# 17_POWER-FILTER_LDO.net
KiCad netlist of a schematic drawn in Altium Designer
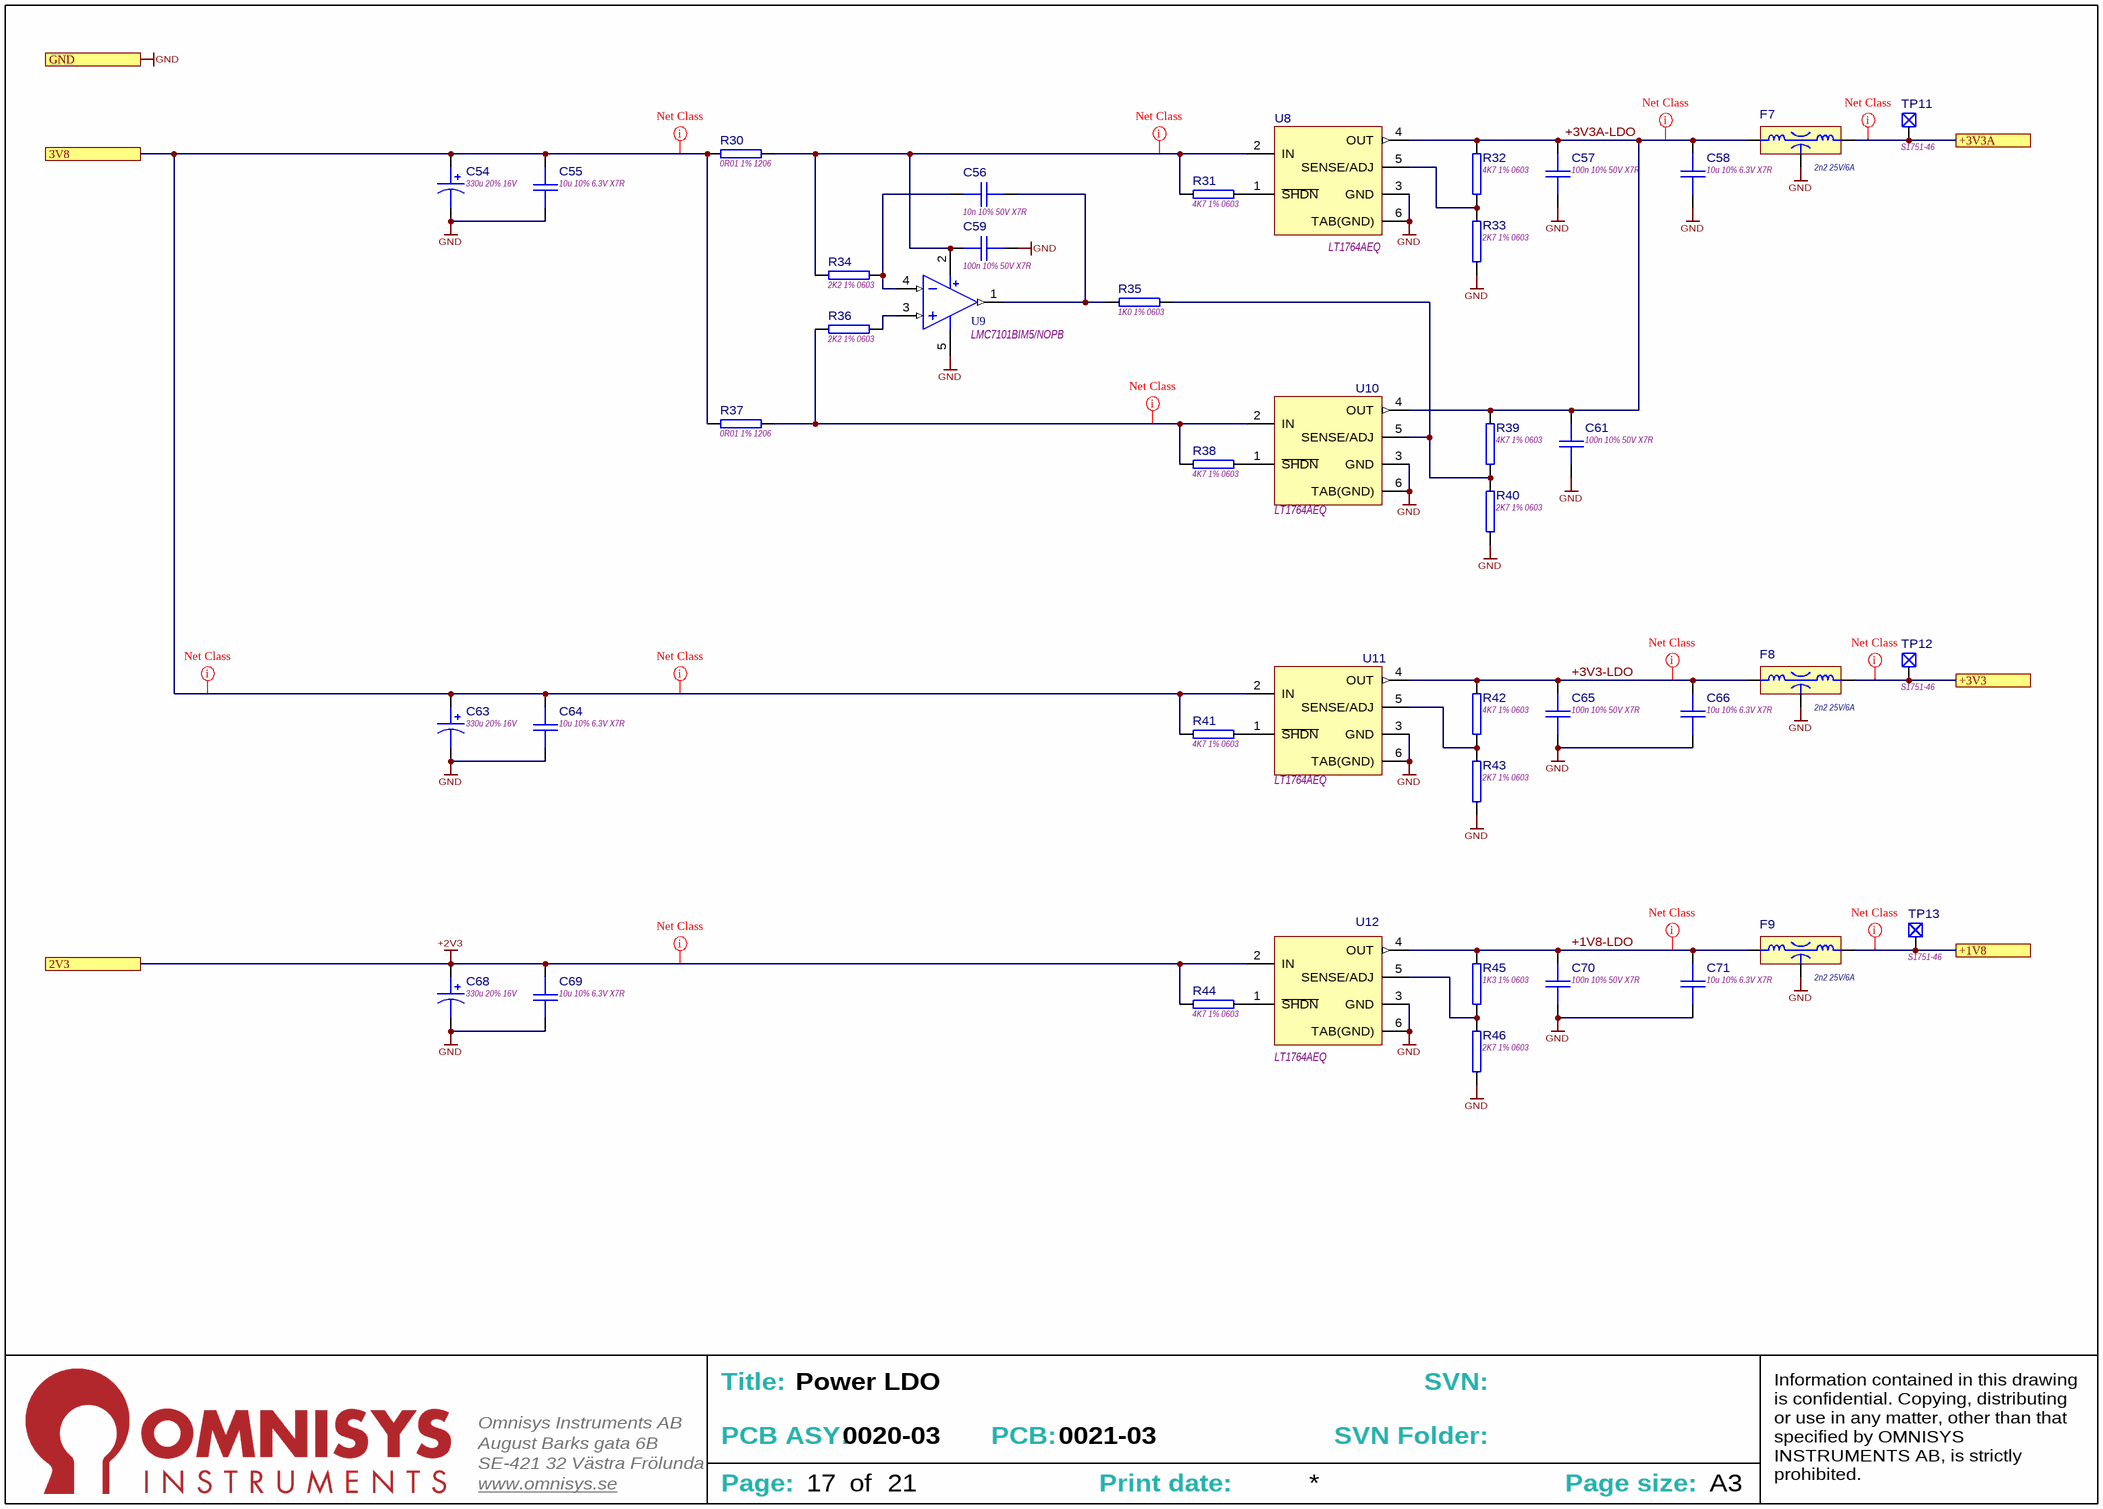
[diagram p0: [17] POWER-FILTER_LDO.SchDoc]

(export (version "E")
  (design (tool "Eeschema 10.0.6"))
  (components
    (comp (ref "C54")
      (value "330u 20% 16V")
      (footprint "CAPMP7343X43N")
      (description "Standard tantalum capacitor, 7343/Case E")
      (fields (field (name "TOLERANCE") "20%"))
      (libsource (lib "Omnisys Vault") (part "CAP-2PIN-POL"))
    )
    (comp (ref "C55")
      (value "10u 10% 6.3V X7R")
      (footprint "CAPC2012X145N")
      (description "Ceramic Chip Capacitor, 0805/2012")
      (fields (field (name "TOLERANCE") "10%"))
      (libsource (lib "Omnisys Vault") (part "CAP-2PIN"))
    )
    (comp (ref "C56")
      (value "10n 10% 50V X7R")
      (footprint "CAPC1608X90N")
      (description "Ceramic Chip Capacitor, 0603/1608")
      (fields (field (name "TOLERANCE") "5%"))
      (libsource (lib "Omnisys Vault") (part "CAP-2PIN"))
    )
    (comp (ref "C57")
      (value "100n 10% 50V X7R")
      (footprint "CAPC1608X90N")
      (description "Ceramic Chip Capacitor, 0603/1608")
      (fields (field (name "TOLERANCE") "10%"))
      (libsource (lib "Omnisys Vault") (part "CAP-2PIN"))
    )
    (comp (ref "C58")
      (value "10u 10% 6.3V X7R")
      (footprint "CAPC2012X145N")
      (description "Ceramic Chip Capacitor, 0805/2012")
      (fields (field (name "TOLERANCE") "10%"))
      (libsource (lib "Omnisys Vault") (part "CAP-2PIN"))
    )
    (comp (ref "C59")
      (value "100n 10% 50V X7R")
      (footprint "CAPC1608X90N")
      (description "Ceramic Chip Capacitor, 0603/1608")
      (fields (field (name "TOLERANCE") "10%"))
      (libsource (lib "Omnisys Vault") (part "CAP-2PIN"))
    )
    (comp (ref "C61")
      (value "100n 10% 50V X7R")
      (footprint "CAPC1608X90N")
      (description "Ceramic Chip Capacitor, 0603/1608")
      (fields (field (name "TOLERANCE") "10%"))
      (libsource (lib "Omnisys Vault") (part "CAP-2PIN"))
    )
    (comp (ref "C63")
      (value "330u 20% 16V")
      (footprint "CAPMP7343X43N")
      (description "Standard tantalum capacitor, 7343/Case E")
      (fields (field (name "TOLERANCE") "20%"))
      (libsource (lib "Omnisys Vault") (part "CAP-2PIN-POL"))
    )
    (comp (ref "C64")
      (value "10u 10% 6.3V X7R")
      (footprint "CAPC2012X145N")
      (description "Ceramic Chip Capacitor, 0805/2012")
      (fields (field (name "TOLERANCE") "10%"))
      (libsource (lib "Omnisys Vault") (part "CAP-2PIN"))
    )
    (comp (ref "C65")
      (value "100n 10% 50V X7R")
      (footprint "CAPC1608X90N")
      (description "Ceramic Chip Capacitor, 0603/1608")
      (fields (field (name "TOLERANCE") "10%"))
      (libsource (lib "Omnisys Vault") (part "CAP-2PIN"))
    )
    (comp (ref "C66")
      (value "10u 10% 6.3V X7R")
      (footprint "CAPC2012X145N")
      (description "Ceramic Chip Capacitor, 0805/2012")
      (fields (field (name "TOLERANCE") "10%"))
      (libsource (lib "Omnisys Vault") (part "CAP-2PIN"))
    )
    (comp (ref "C68")
      (value "330u 20% 16V")
      (footprint "CAPMP7343X43N")
      (description "Standard tantalum capacitor, 7343/Case E")
      (fields (field (name "TOLERANCE") "20%"))
      (libsource (lib "Omnisys Vault") (part "CAP-2PIN-POL"))
    )
    (comp (ref "C69")
      (value "10u 10% 6.3V X7R")
      (footprint "CAPC2012X145N")
      (description "Ceramic Chip Capacitor, 0805/2012")
      (fields (field (name "TOLERANCE") "10%"))
      (libsource (lib "Omnisys Vault") (part "CAP-2PIN"))
    )
    (comp (ref "C70")
      (value "100n 10% 50V X7R")
      (footprint "CAPC1608X90N")
      (description "Ceramic Chip Capacitor, 0603/1608")
      (fields (field (name "TOLERANCE") "10%"))
      (libsource (lib "Omnisys Vault") (part "CAP-2PIN"))
    )
    (comp (ref "C71")
      (value "10u 10% 6.3V X7R")
      (footprint "CAPC2012X145N")
      (description "Ceramic Chip Capacitor, 0805/2012")
      (fields (field (name "TOLERANCE") "10%"))
      (libsource (lib "Omnisys Vault") (part "CAP-2PIN"))
    )
    (comp (ref "F7")
      (value "2n2 25V/6A")
      (footprint "FIL_NFE31P")
      (description "2n2 +50%-50%  25V/6A NFE31PT222Z1E9 LC Combined Filter Feed through Type")
      (fields (field (name "TOLERANCE") "+50%-50%") (field (name "PARTNUMBER") "NFE31PT222Z1E9"))
      (libsource (lib "Omnisys Vault") (part "EMI-LC-3PIN"))
    )
    (comp (ref "F8")
      (value "2n2 25V/6A")
      (footprint "FIL_NFE31P")
      (description "2n2 +50%-50%  25V/6A NFE31PT222Z1E9 LC Combined Filter Feed through Type")
      (fields (field (name "TOLERANCE") "+50%-50%") (field (name "PARTNUMBER") "NFE31PT222Z1E9"))
      (libsource (lib "Omnisys Vault") (part "EMI-LC-3PIN"))
    )
    (comp (ref "F9")
      (value "2n2 25V/6A")
      (footprint "FIL_NFE31P")
      (description "2n2 +50%-50%  25V/6A NFE31PT222Z1E9 LC Combined Filter Feed through Type")
      (fields (field (name "TOLERANCE") "+50%-50%") (field (name "PARTNUMBER") "NFE31PT222Z1E9"))
      (libsource (lib "Omnisys Vault") (part "EMI-LC-3PIN"))
    )
    (comp (ref "R30")
      (value "0R01 1% 1206")
      (footprint "RESC3216N")
      (description "Thick film Chip Resistor, 1206/3216")
      (fields (field (name "TOLERANCE") "1%") (field (name "POWER") "250mW"))
      (libsource (lib "Omnisys Vault") (part "RES-2PIN"))
    )
    (comp (ref "R31")
      (value "4K7 1% 0603")
      (footprint "RESC1608N")
      (description "Thick film Chip Resistor, 0603/1608")
      (fields (field (name "POWER") "100mW") (field (name "TOLERANCE") "1%"))
      (libsource (lib "Omnisys Vault") (part "RES-2PIN"))
    )
    (comp (ref "R32")
      (value "4K7 1% 0603")
      (footprint "RESC1608N")
      (description "Thick film Chip Resistor, 0603/1608")
      (fields (field (name "POWER") "100mW") (field (name "TOLERANCE") "1%"))
      (libsource (lib "Omnisys Vault") (part "RES-2PIN"))
    )
    (comp (ref "R33")
      (value "2K7 1% 0603")
      (footprint "RESC1608N")
      (description "Thick film Chip Resistor, 0603/1608")
      (fields (field (name "POWER") "100mW") (field (name "TOLERANCE") "1%"))
      (libsource (lib "Omnisys Vault") (part "RES-2PIN"))
    )
    (comp (ref "R34")
      (value "2K2 1% 0603")
      (footprint "RESC1608N")
      (description "Thick film Chip Resistor, 0603/1608")
      (fields (field (name "POWER") "100mW") (field (name "TOLERANCE") "1%"))
      (libsource (lib "Omnisys Vault") (part "RES-2PIN"))
    )
    (comp (ref "R35")
      (value "1K0 1% 0603")
      (footprint "RESC1608N")
      (description "Thick film Chip Resistor, 0603/1608")
      (fields (field (name "TOLERANCE") "1%") (field (name "POWER") "100mW"))
      (libsource (lib "Omnisys Vault") (part "RES-2PIN"))
    )
    (comp (ref "R36")
      (value "2K2 1% 0603")
      (footprint "RESC1608N")
      (description "Thick film Chip Resistor, 0603/1608")
      (fields (field (name "POWER") "100mW") (field (name "TOLERANCE") "1%"))
      (libsource (lib "Omnisys Vault") (part "RES-2PIN"))
    )
    (comp (ref "R37")
      (value "0R01 1% 1206")
      (footprint "RESC3216N")
      (description "Thick film Chip Resistor, 1206/3216")
      (fields (field (name "TOLERANCE") "1%") (field (name "POWER") "250mW"))
      (libsource (lib "Omnisys Vault") (part "RES-2PIN"))
    )
    (comp (ref "R38")
      (value "4K7 1% 0603")
      (footprint "RESC1608N")
      (description "Thick film Chip Resistor, 0603/1608")
      (fields (field (name "POWER") "100mW") (field (name "TOLERANCE") "1%"))
      (libsource (lib "Omnisys Vault") (part "RES-2PIN"))
    )
    (comp (ref "R39")
      (value "4K7 1% 0603")
      (footprint "RESC1608N")
      (description "Thick film Chip Resistor, 0603/1608")
      (fields (field (name "POWER") "100mW") (field (name "TOLERANCE") "1%"))
      (libsource (lib "Omnisys Vault") (part "RES-2PIN"))
    )
    (comp (ref "R40")
      (value "2K7 1% 0603")
      (footprint "RESC1608N")
      (description "Thick film Chip Resistor, 0603/1608")
      (fields (field (name "POWER") "100mW") (field (name "TOLERANCE") "1%"))
      (libsource (lib "Omnisys Vault") (part "RES-2PIN"))
    )
    (comp (ref "R41")
      (value "4K7 1% 0603")
      (footprint "RESC1608N")
      (description "Thick film Chip Resistor, 0603/1608")
      (fields (field (name "POWER") "100mW") (field (name "TOLERANCE") "1%"))
      (libsource (lib "Omnisys Vault") (part "RES-2PIN"))
    )
    (comp (ref "R42")
      (value "4K7 1% 0603")
      (footprint "RESC1608N")
      (description "Thick film Chip Resistor, 0603/1608")
      (fields (field (name "POWER") "100mW") (field (name "TOLERANCE") "1%"))
      (libsource (lib "Omnisys Vault") (part "RES-2PIN"))
    )
    (comp (ref "R43")
      (value "2K7 1% 0603")
      (footprint "RESC1608N")
      (description "Thick film Chip Resistor, 0603/1608")
      (fields (field (name "POWER") "100mW") (field (name "TOLERANCE") "1%"))
      (libsource (lib "Omnisys Vault") (part "RES-2PIN"))
    )
    (comp (ref "R44")
      (value "4K7 1% 0603")
      (footprint "RESC1608N")
      (description "Thick film Chip Resistor, 0603/1608")
      (fields (field (name "POWER") "100mW") (field (name "TOLERANCE") "1%"))
      (libsource (lib "Omnisys Vault") (part "RES-2PIN"))
    )
    (comp (ref "R45")
      (value "1K3 1% 0603")
      (footprint "RESC1608N")
      (description "Thick film Chip Resistor, 0603/1608")
      (fields (field (name "POWER") "100mW") (field (name "TOLERANCE") "1%"))
      (libsource (lib "Omnisys Vault") (part "RES-2PIN"))
    )
    (comp (ref "R46")
      (value "2K7 1% 0603")
      (footprint "RESC1608N")
      (description "Thick film Chip Resistor, 0603/1608")
      (fields (field (name "POWER") "100mW") (field (name "TOLERANCE") "1%"))
      (libsource (lib "Omnisys Vault") (part "RES-2PIN"))
    )
    (comp (ref "TP11")
      (value "S1751-46")
      (footprint "S1751-46")
      (description "SMD Test point clip")
      (libsource (lib "Omnisys Vault") (part "1-PIN_TP"))
    )
    (comp (ref "TP12")
      (value "S1751-46")
      (footprint "S1751-46")
      (description "SMD Test point clip")
      (libsource (lib "Omnisys Vault") (part "1-PIN_TP"))
    )
    (comp (ref "TP13")
      (value "S1751-46")
      (footprint "S1751-46")
      (description "SMD Test point clip")
      (libsource (lib "Omnisys Vault") (part "1-PIN_TP"))
    )
    (comp (ref "U8")
      (value "LT1764AEQ")
      (footprint "TO170P1394X457-6N")
      (description "3A, Fast Transient Respons, Low noise LOD regulator")
      (libsource (lib "Omnisys Vault") (part "LT1764"))
    )
    (comp (ref "U9")
      (value "LMC7101BIM5/NOPB")
      (footprint "SOT95P280X100-5N")
      (description "IC, OP AMP, SINGLE, 1MHZ, SMD")
      (libsource (lib "Omnisys Vault") (part "AMP-OPA-LMC7101-5"))
    )
    (comp (ref "U10")
      (value "LT1764AEQ")
      (footprint "TO170P1394X457-6N")
      (description "3A, Fast Transient Respons, Low noise LOD regulator")
      (libsource (lib "Omnisys Vault") (part "LT1764"))
    )
    (comp (ref "U11")
      (value "LT1764AEQ")
      (footprint "TO170P1394X457-6N")
      (description "3A, Fast Transient Respons, Low noise LOD regulator")
      (libsource (lib "Omnisys Vault") (part "LT1764"))
    )
    (comp (ref "U12")
      (value "LT1764AEQ")
      (footprint "TO170P1394X457-6N")
      (description "3A, Fast Transient Respons, Low noise LOD regulator")
      (libsource (lib "Omnisys Vault") (part "LT1764"))
    )
  )
  (nets
    (net (code "1") (name "+2V3") (class "Default")
      (node (ref "C68") (pin "1") (pinfunction "1_1") (pintype "passive"))
      (node (ref "C69") (pin "1") (pinfunction "1_1") (pintype "passive"))
      (node (ref "R44") (pin "1") (pinfunction "1_1") (pintype "passive"))
      (node (ref "U12") (pin "2") (pinfunction "IN_2") (pintype "passive"))
    )
    (net (code "2") (name "/+1V8") (class "Default")
      (node (ref "F9") (pin "2") (pinfunction "Out_2") (pintype "passive"))
      (node (ref "TP13") (pin "1") (pinfunction "1_1") (pintype "passive"))
    )
    (net (code "3") (name "/+1V8-LDO") (class "Default")
      (node (ref "C70") (pin "2") (pinfunction "2_2") (pintype "passive"))
      (node (ref "C71") (pin "1") (pinfunction "1_1") (pintype "passive"))
      (node (ref "F9") (pin "1") (pinfunction "In_1") (pintype "passive"))
      (node (ref "R45") (pin "1") (pinfunction "1_1") (pintype "passive"))
      (node (ref "U12") (pin "4") (pinfunction "OUT_4") (pintype "output"))
    )
    (net (code "4") (name "/+3V3") (class "Default")
      (node (ref "F8") (pin "2") (pinfunction "Out_2") (pintype "passive"))
      (node (ref "TP12") (pin "1") (pinfunction "1_1") (pintype "passive"))
    )
    (net (code "5") (name "/+3V3-LDO") (class "Default")
      (node (ref "C65") (pin "2") (pinfunction "2_2") (pintype "passive"))
      (node (ref "C66") (pin "1") (pinfunction "1_1") (pintype "passive"))
      (node (ref "F8") (pin "1") (pinfunction "In_1") (pintype "passive"))
      (node (ref "R42") (pin "1") (pinfunction "1_1") (pintype "passive"))
      (node (ref "U11") (pin "4") (pinfunction "OUT_4") (pintype "output"))
    )
    (net (code "6") (name "/+3V3A") (class "Default")
      (node (ref "F7") (pin "2") (pinfunction "Out_2") (pintype "passive"))
      (node (ref "TP11") (pin "1") (pinfunction "1_1") (pintype "passive"))
    )
    (net (code "7") (name "/+3V3A-LDO") (class "Default")
      (node (ref "C57") (pin "1") (pinfunction "1_1") (pintype "passive"))
      (node (ref "C58") (pin "1") (pinfunction "1_1") (pintype "passive"))
      (node (ref "C61") (pin "1") (pinfunction "1_1") (pintype "passive"))
      (node (ref "F7") (pin "1") (pinfunction "In_1") (pintype "passive"))
      (node (ref "R32") (pin "1") (pinfunction "1_1") (pintype "passive"))
      (node (ref "R39") (pin "1") (pinfunction "1_1") (pintype "passive"))
      (node (ref "U10") (pin "4") (pinfunction "OUT_4") (pintype "output"))
      (node (ref "U8") (pin "4") (pinfunction "OUT_4") (pintype "output"))
    )
    (net (code "8") (name "/3V8") (class "Default")
      (node (ref "C54") (pin "1") (pinfunction "1_1") (pintype "passive"))
      (node (ref "C55") (pin "1") (pinfunction "1_1") (pintype "passive"))
      (node (ref "C63") (pin "1") (pinfunction "1_1") (pintype "passive"))
      (node (ref "C64") (pin "1") (pinfunction "1_1") (pintype "passive"))
      (node (ref "R30") (pin "1") (pinfunction "1_1") (pintype "passive"))
      (node (ref "R37") (pin "1") (pinfunction "1_1") (pintype "passive"))
      (node (ref "R41") (pin "1") (pinfunction "1_1") (pintype "passive"))
      (node (ref "U11") (pin "2") (pinfunction "IN_2") (pintype "passive"))
    )
    (net (code "9") (name "GND") (class "Default")
      (node (ref "C54") (pin "2") (pinfunction "2_2") (pintype "passive"))
      (node (ref "C55") (pin "2") (pinfunction "2_2") (pintype "passive"))
      (node (ref "C57") (pin "2") (pinfunction "2_2") (pintype "passive"))
      (node (ref "C58") (pin "2") (pinfunction "2_2") (pintype "passive"))
      (node (ref "C59") (pin "2") (pinfunction "2_2") (pintype "passive"))
      (node (ref "C61") (pin "2") (pinfunction "2_2") (pintype "passive"))
      (node (ref "C63") (pin "2") (pinfunction "2_2") (pintype "passive"))
      (node (ref "C64") (pin "2") (pinfunction "2_2") (pintype "passive"))
      (node (ref "C65") (pin "1") (pinfunction "1_1") (pintype "passive"))
      (node (ref "C66") (pin "2") (pinfunction "2_2") (pintype "passive"))
      (node (ref "C68") (pin "2") (pinfunction "2_2") (pintype "passive"))
      (node (ref "C69") (pin "2") (pinfunction "2_2") (pintype "passive"))
      (node (ref "C70") (pin "1") (pinfunction "1_1") (pintype "passive"))
      (node (ref "C71") (pin "2") (pinfunction "2_2") (pintype "passive"))
      (node (ref "F7") (pin "3") (pinfunction "Gnd_3") (pintype "passive"))
      (node (ref "F8") (pin "3") (pinfunction "Gnd_3") (pintype "passive"))
      (node (ref "F9") (pin "3") (pinfunction "Gnd_3") (pintype "passive"))
      (node (ref "R33") (pin "2") (pinfunction "2_2") (pintype "passive"))
      (node (ref "R40") (pin "2") (pinfunction "2_2") (pintype "passive"))
      (node (ref "R43") (pin "2") (pinfunction "2_2") (pintype "passive"))
      (node (ref "R46") (pin "2") (pinfunction "2_2") (pintype "passive"))
      (node (ref "U10") (pin "3") (pinfunction "GND_3") (pintype "passive"))
      (node (ref "U10") (pin "6") (pinfunction "TAB(GND)_6") (pintype "passive"))
      (node (ref "U11") (pin "3") (pinfunction "GND_3") (pintype "passive"))
      (node (ref "U11") (pin "6") (pinfunction "TAB(GND)_6") (pintype "passive"))
      (node (ref "U12") (pin "3") (pinfunction "GND_3") (pintype "passive"))
      (node (ref "U12") (pin "6") (pinfunction "TAB(GND)_6") (pintype "passive"))
      (node (ref "U8") (pin "3") (pinfunction "GND_3") (pintype "passive"))
      (node (ref "U8") (pin "6") (pinfunction "TAB(GND)_6") (pintype "passive"))
      (node (ref "U9") (pin "5") (pinfunction "V-_5") (pintype "power_in"))
    )
    (net (code "10") (name "Net-(U8-IN)") (class "Default")
      (node (ref "C59") (pin "1") (pinfunction "1_1") (pintype "passive"))
      (node (ref "R30") (pin "2") (pinfunction "2_2") (pintype "passive"))
      (node (ref "R31") (pin "1") (pinfunction "1_1") (pintype "passive"))
      (node (ref "R34") (pin "1") (pinfunction "1_1") (pintype "passive"))
      (node (ref "U8") (pin "2") (pinfunction "IN_2") (pintype "passive"))
      (node (ref "U9") (pin "2") (pinfunction "V+_2") (pintype "power_in"))
    )
    (net (code "11") (name "Net-(U8-SENSE{slash}ADJ)") (class "Default")
      (node (ref "R32") (pin "2") (pinfunction "2_2") (pintype "passive"))
      (node (ref "R33") (pin "1") (pinfunction "1_1") (pintype "passive"))
      (node (ref "U8") (pin "5") (pinfunction "SENSE/ADJ_5") (pintype "passive"))
    )
    (net (code "12") (name "Net-(U8-~{SHDN})") (class "Default")
      (node (ref "R31") (pin "2") (pinfunction "2_2") (pintype "passive"))
      (node (ref "U8") (pin "1") (pinfunction "~{SHDN}_1") (pintype "passive"))
    )
    (net (code "13") (name "Net-(U9-IN+)") (class "Default")
      (node (ref "R36") (pin "2") (pinfunction "2_2") (pintype "passive"))
      (node (ref "U9") (pin "3") (pinfunction "IN+_3") (pintype "input"))
    )
    (net (code "14") (name "Net-(U9-IN-)") (class "Default")
      (node (ref "C56") (pin "1") (pinfunction "1_1") (pintype "passive"))
      (node (ref "R34") (pin "2") (pinfunction "2_2") (pintype "passive"))
      (node (ref "U9") (pin "4") (pinfunction "IN-_4") (pintype "input"))
    )
    (net (code "15") (name "Net-(U9-OUT)") (class "Default")
      (node (ref "C56") (pin "2") (pinfunction "2_2") (pintype "passive"))
      (node (ref "R35") (pin "1") (pinfunction "1_1") (pintype "passive"))
      (node (ref "U9") (pin "1") (pinfunction "OUT_1") (pintype "output"))
    )
    (net (code "16") (name "Net-(U10-IN)") (class "Default")
      (node (ref "R36") (pin "1") (pinfunction "1_1") (pintype "passive"))
      (node (ref "R37") (pin "2") (pinfunction "2_2") (pintype "passive"))
      (node (ref "R38") (pin "1") (pinfunction "1_1") (pintype "passive"))
      (node (ref "U10") (pin "2") (pinfunction "IN_2") (pintype "passive"))
    )
    (net (code "17") (name "Net-(U10-SENSE{slash}ADJ)") (class "Default")
      (node (ref "R35") (pin "2") (pinfunction "2_2") (pintype "passive"))
      (node (ref "R39") (pin "2") (pinfunction "2_2") (pintype "passive"))
      (node (ref "R40") (pin "1") (pinfunction "1_1") (pintype "passive"))
      (node (ref "U10") (pin "5") (pinfunction "SENSE/ADJ_5") (pintype "passive"))
    )
    (net (code "18") (name "Net-(U10-~{SHDN})") (class "Default")
      (node (ref "R38") (pin "2") (pinfunction "2_2") (pintype "passive"))
      (node (ref "U10") (pin "1") (pinfunction "~{SHDN}_1") (pintype "passive"))
    )
    (net (code "19") (name "Net-(U11-SENSE{slash}ADJ)") (class "Default")
      (node (ref "R42") (pin "2") (pinfunction "2_2") (pintype "passive"))
      (node (ref "R43") (pin "1") (pinfunction "1_1") (pintype "passive"))
      (node (ref "U11") (pin "5") (pinfunction "SENSE/ADJ_5") (pintype "passive"))
    )
    (net (code "20") (name "Net-(U11-~{SHDN})") (class "Default")
      (node (ref "R41") (pin "2") (pinfunction "2_2") (pintype "passive"))
      (node (ref "U11") (pin "1") (pinfunction "~{SHDN}_1") (pintype "passive"))
    )
    (net (code "21") (name "Net-(U12-SENSE{slash}ADJ)") (class "Default")
      (node (ref "R45") (pin "2") (pinfunction "2_2") (pintype "passive"))
      (node (ref "R46") (pin "1") (pinfunction "1_1") (pintype "passive"))
      (node (ref "U12") (pin "5") (pinfunction "SENSE/ADJ_5") (pintype "passive"))
    )
    (net (code "22") (name "Net-(U12-~{SHDN})") (class "Default")
      (node (ref "R44") (pin "2") (pinfunction "2_2") (pintype "passive"))
      (node (ref "U12") (pin "1") (pinfunction "~{SHDN}_1") (pintype "passive"))
    )
  )
)
